# CPU_Programmer_Schem.net
KiCad netlist of a schematic drawn in Altium Designer
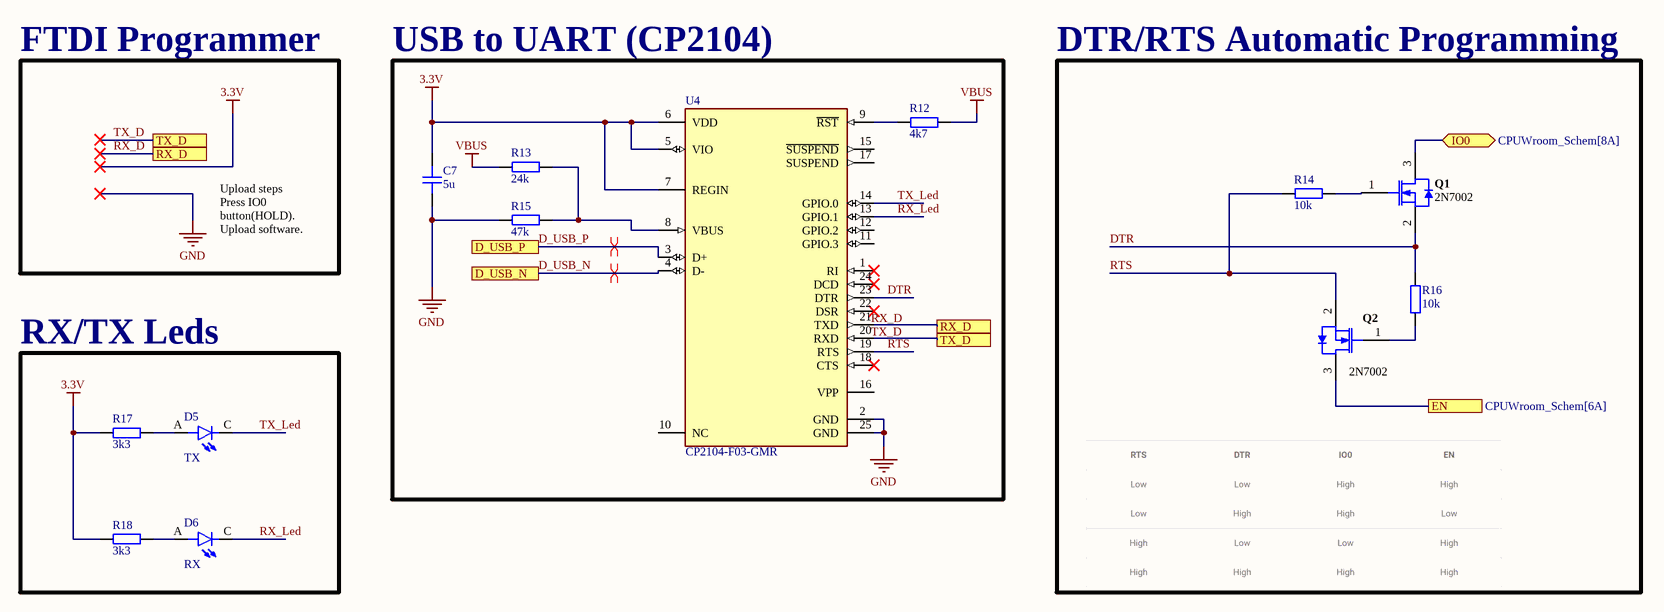
[diagram p0: CPU_Programmer_Schem.SchDoc]

(export (version "E")
  (design (tool "Eeschema 10.0.6"))
  (components
    (comp (ref "C7")
      (value "5u")
      (footprint "CAP_1206")
      (description "Capacitor SMD 1206 50V")
      (libsource (lib "Schem_Lib_DaanHeetkamp.") (part "CAP_1206_50V"))
    )
    (comp (ref "D5")
      (value "TX")
      (footprint "PCB_Lib_DaanHeetkamp:LED_1206")
      (description "Yellow 587nm LED Indication - Discrete 2V 1206 _3216 Metric_")
      (fields (field (name "MF") "Lite-On Inc.") (field (name "MP") "LTST-C230KSKT"))
      (libsource (lib "Schem_Lib_DaanHeetkamp.") (part "LED - 1206"))
    )
    (comp (ref "D6")
      (value "RX")
      (footprint "PCB_Lib_DaanHeetkamp:LED_1206")
      (description "Yellow 587nm LED Indication - Discrete 2V 1206 _3216 Metric_")
      (fields (field (name "MF") "Lite-On Inc.") (field (name "MP") "LTST-C230KSKT"))
      (libsource (lib "Schem_Lib_DaanHeetkamp.") (part "LED - 1206"))
    )
    (comp (ref "Q1")
      (value "2N7002")
      (footprint "INF-PG-SOT23_M")
      (fields (field (name "MANUFACTURER") "Infineon"))
      (libsource (lib "Altium Content Vault") (part "INF-NDMOS-GSD-3"))
    )
    (comp (ref "Q2")
      (value "2N7002")
      (footprint "INF-PG-SOT23_M")
      (fields (field (name "MANUFACTURER") "Infineon"))
      (libsource (lib "Altium Content Vault") (part "INF-NDMOS-GSD-3"))
    )
    (comp (ref "R12")
      (value "4k7")
      (footprint "RES_1206")
      (description "Resistor SMD 1206")
      (libsource (lib "Schem_Lib_DaanHeetkamp.") (part "RES_1206"))
    )
    (comp (ref "R13")
      (value "24k")
      (footprint "RES_1206")
      (description "Resistor SMD 1206")
      (libsource (lib "Schem_Lib_DaanHeetkamp.") (part "RES_1206"))
    )
    (comp (ref "R14")
      (value "10k")
      (footprint "RES_1206")
      (description "Resistor SMD 1206")
      (libsource (lib "Schem_Lib_DaanHeetkamp.") (part "RES_1206"))
    )
    (comp (ref "R15")
      (value "47k")
      (footprint "RES_1206")
      (description "Resistor SMD 1206")
      (libsource (lib "Schem_Lib_DaanHeetkamp.") (part "RES_1206"))
    )
    (comp (ref "R16")
      (value "10k")
      (footprint "RES_1206")
      (description "Resistor SMD 1206")
      (libsource (lib "Schem_Lib_DaanHeetkamp.") (part "RES_1206"))
    )
    (comp (ref "R17")
      (value "3k3")
      (footprint "RES_1206")
      (description "Resistor SMD 1206")
      (libsource (lib "Schem_Lib_DaanHeetkamp.") (part "RES_1206"))
    )
    (comp (ref "R18")
      (value "3k3")
      (footprint "RES_1206")
      (description "Resistor SMD 1206")
      (libsource (lib "Schem_Lib_DaanHeetkamp.") (part "RES_1206"))
    )
    (comp (ref "U4")
      (value "CP2104-F03-GMR")
      (footprint "FP-CP2104-F03-GMR-MFG")
      (description "IC SGL USB-TO-UART BRIDGE 24QFN")
      (fields
        (field (name "OCTOPART") "https://octopart.com/cp2104-f03-gmr-silicon+labs-19668642")
        (field (name "MANUFACTURER") "Silicon Laboratories")
      )
      (libsource (lib "Altium Content Vault") (part "c264a613fa4ce846ece45e07ca4b292"))
    )
  )
  (nets
    (net (code "1") (name "/DTR") (class "Default")
      (node (ref "Q1") (pin "2") (pinfunction "SOURCE_2") (pintype "passive"))
      (node (ref "R16") (pin "1") (pinfunction "1_1") (pintype "passive"))
      (node (ref "U4") (pin "23") (pinfunction "DTR_23") (pintype "output"))
    )
    (net (code "2") (name "/D_USB_N") (class "Default")
      (node (ref "U4") (pin "4") (pinfunction "D-_4") (pintype "bidirectional"))
    )
    (net (code "3") (name "/D_USB_P") (class "Default")
      (node (ref "U4") (pin "3") (pinfunction "D+_3") (pintype "bidirectional"))
    )
    (net (code "4") (name "/EN") (class "Default")
      (node (ref "Q2") (pin "3") (pinfunction "DRAIN_3") (pintype "passive"))
    )
    (net (code "5") (name "/IO0") (class "Default")
      (node (ref "Q1") (pin "3") (pinfunction "DRAIN_3") (pintype "passive"))
    )
    (net (code "6") (name "/RTS") (class "Default")
      (node (ref "Q2") (pin "2") (pinfunction "SOURCE_2") (pintype "passive"))
      (node (ref "R14") (pin "1") (pinfunction "1_1") (pintype "passive"))
      (node (ref "U4") (pin "19") (pinfunction "RTS_19") (pintype "output"))
    )
    (net (code "7") (name "/RX_D") (class "Default")
      (node (ref "U4") (pin "21") (pinfunction "TXD_21") (pintype "output+no_connect"))
    )
    (net (code "8") (name "/RX_Led") (class "Default")
      (node (ref "D6") (pin "C") (pinfunction "C_C") (pintype "passive"))
      (node (ref "U4") (pin "13") (pinfunction "GPIO.1_13") (pintype "bidirectional"))
    )
    (net (code "9") (name "/TX_D") (class "Default")
      (node (ref "U4") (pin "20") (pinfunction "RXD_20") (pintype "input+no_connect"))
    )
    (net (code "10") (name "/TX_Led") (class "Default")
      (node (ref "D5") (pin "C") (pinfunction "C_C") (pintype "passive"))
      (node (ref "U4") (pin "14") (pinfunction "GPIO.0_14") (pintype "bidirectional"))
    )
    (net (code "11") (name "3.3V") (class "Default")
      (node (ref "C7") (pin "2") (pinfunction "2_2") (pintype "passive"))
      (node (ref "R17") (pin "1") (pinfunction "1_1") (pintype "passive"))
      (node (ref "R18") (pin "1") (pinfunction "1_1") (pintype "passive"))
      (node (ref "U4") (pin "5") (pinfunction "VIO_5") (pintype "bidirectional"))
      (node (ref "U4") (pin "6") (pinfunction "VDD_6") (pintype "power_in"))
      (node (ref "U4") (pin "7") (pinfunction "REGIN_7") (pintype "power_in"))
    )
    (net (code "12") (name "GND") (class "Default")
      (node (ref "C7") (pin "1") (pinfunction "1_1") (pintype "passive"))
      (node (ref "R15") (pin "1") (pinfunction "1_1") (pintype "passive"))
      (node (ref "U4") (pin "2") (pinfunction "GND_2") (pintype "power_in"))
      (node (ref "U4") (pin "25") (pinfunction "GND_25") (pintype "power_in"))
    )
    (net (code "13") (name "Net-(D5-PadA)") (class "Default")
      (node (ref "D5") (pin "A") (pinfunction "A_A") (pintype "passive"))
      (node (ref "R17") (pin "2") (pinfunction "2_2") (pintype "passive"))
    )
    (net (code "14") (name "Net-(D6-PadA)") (class "Default")
      (node (ref "D6") (pin "A") (pinfunction "A_A") (pintype "passive"))
      (node (ref "R18") (pin "2") (pinfunction "2_2") (pintype "passive"))
    )
    (net (code "15") (name "Net-(Q1-GATE)") (class "Default")
      (node (ref "Q1") (pin "1") (pinfunction "GATE_1") (pintype "passive"))
      (node (ref "R14") (pin "2") (pinfunction "2_2") (pintype "passive"))
    )
    (net (code "16") (name "Net-(Q2-GATE)") (class "Default")
      (node (ref "Q2") (pin "1") (pinfunction "GATE_1") (pintype "passive"))
      (node (ref "R16") (pin "2") (pinfunction "2_2") (pintype "passive"))
    )
    (net (code "17") (name "Net-(U4-VBUS)") (class "Default")
      (node (ref "R13") (pin "2") (pinfunction "2_2") (pintype "passive"))
      (node (ref "R15") (pin "2") (pinfunction "2_2") (pintype "passive"))
      (node (ref "U4") (pin "8") (pinfunction "VBUS_8") (pintype "input"))
    )
    (net (code "18") (name "Net-(U4-~{RST})") (class "Default")
      (node (ref "R12") (pin "2") (pinfunction "2_2") (pintype "passive"))
      (node (ref "U4") (pin "9") (pinfunction "~{RST}_9") (pintype "input"))
    )
    (net (code "19") (name "VBUS") (class "Default")
      (node (ref "R12") (pin "1") (pinfunction "1_1") (pintype "passive"))
      (node (ref "R13") (pin "1") (pinfunction "1_1") (pintype "passive"))
    )
    (net (code "20") (name "unconnected-(U4-CTS-Pad18)") (class "Default")
      (node (ref "U4") (pin "18") (pinfunction "CTS_18") (pintype "input+no_connect"))
    )
    (net (code "21") (name "unconnected-(U4-DCD-Pad24)") (class "Default")
      (node (ref "U4") (pin "24") (pinfunction "DCD_24") (pintype "input+no_connect"))
    )
    (net (code "22") (name "unconnected-(U4-DSR-Pad22)") (class "Default")
      (node (ref "U4") (pin "22") (pinfunction "DSR_22") (pintype "input+no_connect"))
    )
    (net (code "23") (name "unconnected-(U4-GPIO.2-Pad12)") (class "Default")
      (node (ref "U4") (pin "12") (pinfunction "GPIO.2_12") (pintype "bidirectional"))
    )
    (net (code "24") (name "unconnected-(U4-GPIO.3-Pad11)") (class "Default")
      (node (ref "U4") (pin "11") (pinfunction "GPIO.3_11") (pintype "bidirectional"))
    )
    (net (code "25") (name "unconnected-(U4-NC-Pad10)") (class "Default")
      (node (ref "U4") (pin "10") (pinfunction "NC_10") (pintype "passive"))
    )
    (net (code "26") (name "unconnected-(U4-RI-Pad1)") (class "Default")
      (node (ref "U4") (pin "1") (pinfunction "RI_1") (pintype "input+no_connect"))
    )
    (net (code "27") (name "unconnected-(U4-SUSPEND-Pad17)") (class "Default")
      (node (ref "U4") (pin "17") (pinfunction "SUSPEND_17") (pintype "output"))
    )
    (net (code "28") (name "unconnected-(U4-VPP-Pad16)") (class "Default")
      (node (ref "U4") (pin "16") (pinfunction "VPP_16") (pintype "power_in"))
    )
    (net (code "29") (name "unconnected-(U4-~{SUSPEND}-Pad15)") (class "Default")
      (node (ref "U4") (pin "15") (pinfunction "~{SUSPEND}_15") (pintype "output"))
    )
  )
)
